# Schematic.net
KiCad netlist of a schematic drawn in EasyEDA
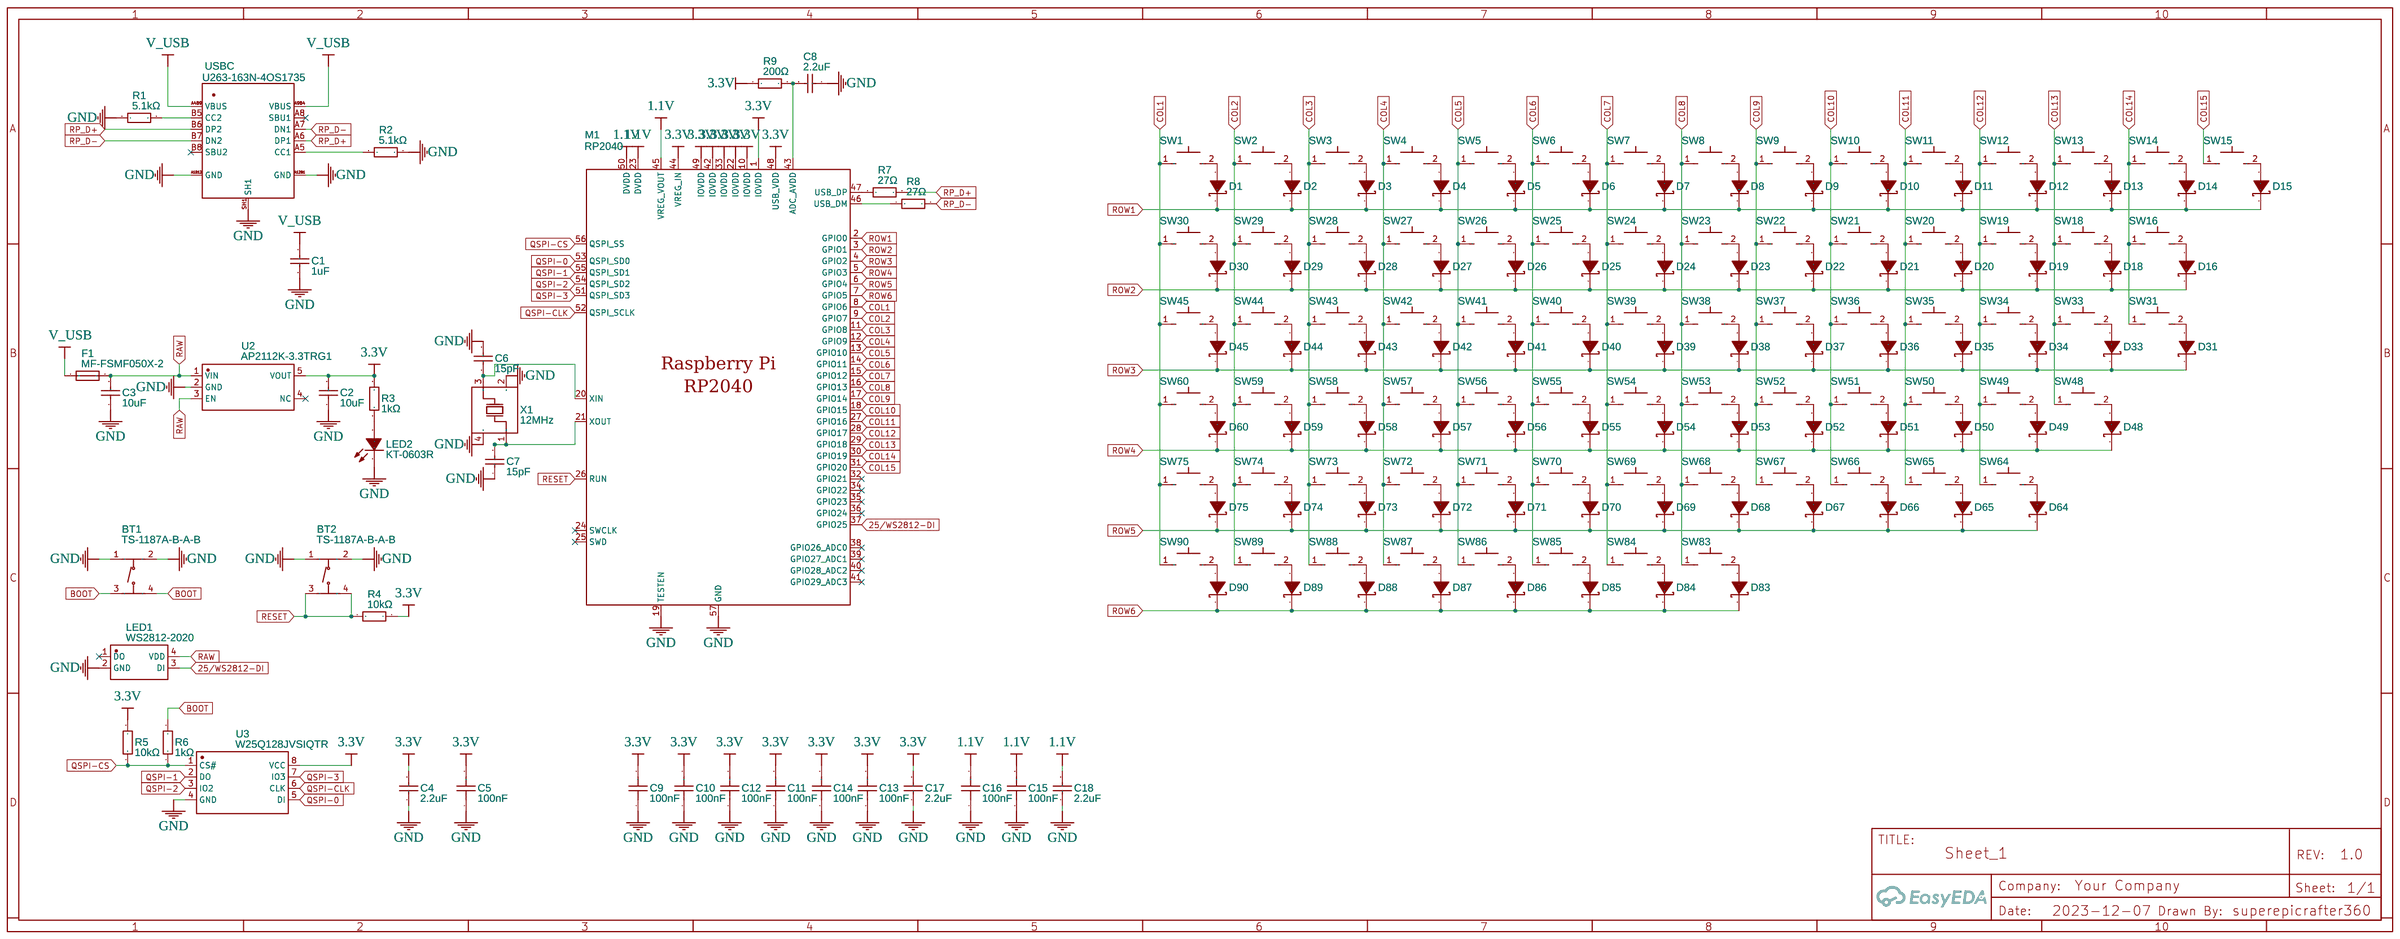
[diagram p0: schematic sheet]

(export (version "E")
  (design (tool "Eeschema 10.0.6"))
  (components
    (comp (ref "BT1")
      (value "TS-1187A-B-A-B")
      (fields (field (name "Manufacturer") "XKB Connectivity(中国星坤)"))
      (libsource (lib "") (part "TS-1187A-B-A-B"))
    )
    (comp (ref "BT2")
      (value "TS-1187A-B-A-B")
      (fields (field (name "Manufacturer") "XKB Connectivity(中国星坤)"))
      (libsource (lib "") (part "TS-1187A-B-A-B"))
    )
    (comp (ref "C1")
      (value "1uF")
      (fields
        (field (name "Manufacturer Part") "CL10A105KB8NNNC")
        (field (name "Manufacturer") "SAMSUNG(三星)")
      )
      (libsource (lib "") (part "CL10A105KB8NNNC"))
    )
    (comp (ref "C2")
      (value "10uF")
      (fields
        (field (name "Manufacturer Part") "CL31A106KBHNNNE")
        (field (name "Manufacturer") "SAMSUNG(三星)")
      )
      (libsource (lib "") (part "CL31A106KBHNNNE"))
    )
    (comp (ref "C3")
      (value "10uF")
      (fields
        (field (name "Manufacturer Part") "CL31A106KBHNNNE")
        (field (name "Manufacturer") "SAMSUNG(三星)")
      )
      (libsource (lib "") (part "CL31A106KBHNNNE"))
    )
    (comp (ref "C4")
      (value "2.2uF")
      (fields
        (field (name "Manufacturer Part") "CL10A225KO8NNNC")
        (field (name "Manufacturer") "SAMSUNG(三星)")
      )
      (libsource (lib "") (part "CL10A225KO8NNNC"))
    )
    (comp (ref "C5")
      (value "100nF")
      (fields
        (field (name "Manufacturer Part") "CC0603KRX7R9BB104")
        (field (name "Manufacturer") "YAGEO(国巨)")
      )
      (libsource (lib "") (part "CC0603KRX7R9BB104"))
    )
    (comp (ref "C6")
      (value "15pF")
      (fields (field (name "Manufacturer Part") "0402CG150J500NT") (field (name "Manufacturer") "FH(风华)"))
      (libsource (lib "") (part "0402CG150J500NT"))
    )
    (comp (ref "C7")
      (value "15pF")
      (fields (field (name "Manufacturer Part") "0402CG150J500NT") (field (name "Manufacturer") "FH(风华)"))
      (libsource (lib "") (part "0402CG150J500NT"))
    )
    (comp (ref "C8")
      (value "2.2uF")
      (fields
        (field (name "Manufacturer Part") "CL10A225KO8NNNC")
        (field (name "Manufacturer") "SAMSUNG(三星)")
      )
      (libsource (lib "") (part "CL10A225KO8NNNC_1"))
    )
    (comp (ref "C9")
      (value "100nF")
      (fields
        (field (name "Manufacturer Part") "CC0603KRX7R9BB104")
        (field (name "Manufacturer") "YAGEO(国巨)")
      )
      (libsource (lib "") (part "CC0603KRX7R9BB104"))
    )
    (comp (ref "C10")
      (value "100nF")
      (fields
        (field (name "Manufacturer Part") "CC0603KRX7R9BB104")
        (field (name "Manufacturer") "YAGEO(国巨)")
      )
      (libsource (lib "") (part "CC0603KRX7R9BB104"))
    )
    (comp (ref "C11")
      (value "100nF")
      (fields
        (field (name "Manufacturer Part") "CC0603KRX7R9BB104")
        (field (name "Manufacturer") "YAGEO(国巨)")
      )
      (libsource (lib "") (part "CC0603KRX7R9BB104"))
    )
    (comp (ref "C12")
      (value "100nF")
      (fields
        (field (name "Manufacturer Part") "CC0603KRX7R9BB104")
        (field (name "Manufacturer") "YAGEO(国巨)")
      )
      (libsource (lib "") (part "CC0603KRX7R9BB104"))
    )
    (comp (ref "C13")
      (value "100nF")
      (fields
        (field (name "Manufacturer Part") "CC0603KRX7R9BB104")
        (field (name "Manufacturer") "YAGEO(国巨)")
      )
      (libsource (lib "") (part "CC0603KRX7R9BB104"))
    )
    (comp (ref "C14")
      (value "100nF")
      (fields
        (field (name "Manufacturer Part") "CC0603KRX7R9BB104")
        (field (name "Manufacturer") "YAGEO(国巨)")
      )
      (libsource (lib "") (part "CC0603KRX7R9BB104"))
    )
    (comp (ref "C15")
      (value "100nF")
      (fields
        (field (name "Manufacturer Part") "CC0603KRX7R9BB104")
        (field (name "Manufacturer") "YAGEO(国巨)")
      )
      (libsource (lib "") (part "CC0603KRX7R9BB104"))
    )
    (comp (ref "C16")
      (value "100nF")
      (fields
        (field (name "Manufacturer Part") "CC0603KRX7R9BB104")
        (field (name "Manufacturer") "YAGEO(国巨)")
      )
      (libsource (lib "") (part "CC0603KRX7R9BB104"))
    )
    (comp (ref "C17")
      (value "2.2uF")
      (fields
        (field (name "Manufacturer Part") "CL10A225KO8NNNC")
        (field (name "Manufacturer") "SAMSUNG(三星)")
      )
      (libsource (lib "") (part "CL10A225KO8NNNC"))
    )
    (comp (ref "C18")
      (value "2.2uF")
      (fields
        (field (name "Manufacturer Part") "CL10A225KO8NNNC")
        (field (name "Manufacturer") "SAMSUNG(三星)")
      )
      (libsource (lib "") (part "CL10A225KO8NNNC"))
    )
    (comp (ref "D1")
      (value "SS210")
      (fields (field (name "Manufacturer") "MDD"))
      (libsource (lib "") (part "SS210"))
    )
    (comp (ref "D2")
      (value "SS210")
      (fields (field (name "Manufacturer") "MDD"))
      (libsource (lib "") (part "SS210"))
    )
    (comp (ref "D3")
      (value "SS210")
      (fields (field (name "Manufacturer") "MDD"))
      (libsource (lib "") (part "SS210"))
    )
    (comp (ref "D4")
      (value "SS210")
      (fields (field (name "Manufacturer") "MDD"))
      (libsource (lib "") (part "SS210"))
    )
    (comp (ref "D5")
      (value "SS210")
      (fields (field (name "Manufacturer") "MDD"))
      (libsource (lib "") (part "SS210"))
    )
    (comp (ref "D6")
      (value "SS210")
      (fields (field (name "Manufacturer") "MDD"))
      (libsource (lib "") (part "SS210"))
    )
    (comp (ref "D7")
      (value "SS210")
      (fields (field (name "Manufacturer") "MDD"))
      (libsource (lib "") (part "SS210"))
    )
    (comp (ref "D8")
      (value "SS210")
      (fields (field (name "Manufacturer") "MDD"))
      (libsource (lib "") (part "SS210"))
    )
    (comp (ref "D9")
      (value "SS210")
      (fields (field (name "Manufacturer") "MDD"))
      (libsource (lib "") (part "SS210"))
    )
    (comp (ref "D10")
      (value "SS210")
      (fields (field (name "Manufacturer") "MDD"))
      (libsource (lib "") (part "SS210"))
    )
    (comp (ref "D11")
      (value "SS210")
      (fields (field (name "Manufacturer") "MDD"))
      (libsource (lib "") (part "SS210"))
    )
    (comp (ref "D12")
      (value "SS210")
      (fields (field (name "Manufacturer") "MDD"))
      (libsource (lib "") (part "SS210"))
    )
    (comp (ref "D13")
      (value "SS210")
      (fields (field (name "Manufacturer") "MDD"))
      (libsource (lib "") (part "SS210"))
    )
    (comp (ref "D14")
      (value "SS210")
      (fields (field (name "Manufacturer") "MDD"))
      (libsource (lib "") (part "SS210"))
    )
    (comp (ref "D15")
      (value "SS210")
      (fields (field (name "Manufacturer") "MDD"))
      (libsource (lib "") (part "SS210"))
    )
    (comp (ref "D16")
      (value "SS210")
      (fields (field (name "Manufacturer") "MDD"))
      (libsource (lib "") (part "SS210"))
    )
    (comp (ref "D18")
      (value "SS210")
      (fields (field (name "Manufacturer") "MDD"))
      (libsource (lib "") (part "SS210"))
    )
    (comp (ref "D19")
      (value "SS210")
      (fields (field (name "Manufacturer") "MDD"))
      (libsource (lib "") (part "SS210"))
    )
    (comp (ref "D20")
      (value "SS210")
      (fields (field (name "Manufacturer") "MDD"))
      (libsource (lib "") (part "SS210"))
    )
    (comp (ref "D21")
      (value "SS210")
      (fields (field (name "Manufacturer") "MDD"))
      (libsource (lib "") (part "SS210"))
    )
    (comp (ref "D22")
      (value "SS210")
      (fields (field (name "Manufacturer") "MDD"))
      (libsource (lib "") (part "SS210"))
    )
    (comp (ref "D23")
      (value "SS210")
      (fields (field (name "Manufacturer") "MDD"))
      (libsource (lib "") (part "SS210"))
    )
    (comp (ref "D24")
      (value "SS210")
      (fields (field (name "Manufacturer") "MDD"))
      (libsource (lib "") (part "SS210"))
    )
    (comp (ref "D25")
      (value "SS210")
      (fields (field (name "Manufacturer") "MDD"))
      (libsource (lib "") (part "SS210"))
    )
    (comp (ref "D26")
      (value "SS210")
      (fields (field (name "Manufacturer") "MDD"))
      (libsource (lib "") (part "SS210"))
    )
    (comp (ref "D27")
      (value "SS210")
      (fields (field (name "Manufacturer") "MDD"))
      (libsource (lib "") (part "SS210"))
    )
    (comp (ref "D28")
      (value "SS210")
      (fields (field (name "Manufacturer") "MDD"))
      (libsource (lib "") (part "SS210"))
    )
    (comp (ref "D29")
      (value "SS210")
      (fields (field (name "Manufacturer") "MDD"))
      (libsource (lib "") (part "SS210"))
    )
    (comp (ref "D30")
      (value "SS210")
      (fields (field (name "Manufacturer") "MDD"))
      (libsource (lib "") (part "SS210"))
    )
    (comp (ref "D31")
      (value "SS210")
      (fields (field (name "Manufacturer") "MDD"))
      (libsource (lib "") (part "SS210"))
    )
    (comp (ref "D33")
      (value "SS210")
      (fields (field (name "Manufacturer") "MDD"))
      (libsource (lib "") (part "SS210"))
    )
    (comp (ref "D34")
      (value "SS210")
      (fields (field (name "Manufacturer") "MDD"))
      (libsource (lib "") (part "SS210"))
    )
    (comp (ref "D35")
      (value "SS210")
      (fields (field (name "Manufacturer") "MDD"))
      (libsource (lib "") (part "SS210"))
    )
    (comp (ref "D36")
      (value "SS210")
      (fields (field (name "Manufacturer") "MDD"))
      (libsource (lib "") (part "SS210"))
    )
    (comp (ref "D37")
      (value "SS210")
      (fields (field (name "Manufacturer") "MDD"))
      (libsource (lib "") (part "SS210"))
    )
    (comp (ref "D38")
      (value "SS210")
      (fields (field (name "Manufacturer") "MDD"))
      (libsource (lib "") (part "SS210"))
    )
    (comp (ref "D39")
      (value "SS210")
      (fields (field (name "Manufacturer") "MDD"))
      (libsource (lib "") (part "SS210"))
    )
    (comp (ref "D40")
      (value "SS210")
      (fields (field (name "Manufacturer") "MDD"))
      (libsource (lib "") (part "SS210"))
    )
    (comp (ref "D41")
      (value "SS210")
      (fields (field (name "Manufacturer") "MDD"))
      (libsource (lib "") (part "SS210"))
    )
    (comp (ref "D42")
      (value "SS210")
      (fields (field (name "Manufacturer") "MDD"))
      (libsource (lib "") (part "SS210"))
    )
    (comp (ref "D43")
      (value "SS210")
      (fields (field (name "Manufacturer") "MDD"))
      (libsource (lib "") (part "SS210"))
    )
    (comp (ref "D44")
      (value "SS210")
      (fields (field (name "Manufacturer") "MDD"))
      (libsource (lib "") (part "SS210"))
    )
    (comp (ref "D45")
      (value "SS210")
      (fields (field (name "Manufacturer") "MDD"))
      (libsource (lib "") (part "SS210"))
    )
    (comp (ref "D48")
      (value "SS210")
      (fields (field (name "Manufacturer") "MDD"))
      (libsource (lib "") (part "SS210"))
    )
    (comp (ref "D49")
      (value "SS210")
      (fields (field (name "Manufacturer") "MDD"))
      (libsource (lib "") (part "SS210"))
    )
    (comp (ref "D50")
      (value "SS210")
      (fields (field (name "Manufacturer") "MDD"))
      (libsource (lib "") (part "SS210"))
    )
    (comp (ref "D51")
      (value "SS210")
      (fields (field (name "Manufacturer") "MDD"))
      (libsource (lib "") (part "SS210"))
    )
    (comp (ref "D52")
      (value "SS210")
      (fields (field (name "Manufacturer") "MDD"))
      (libsource (lib "") (part "SS210"))
    )
    (comp (ref "D53")
      (value "SS210")
      (fields (field (name "Manufacturer") "MDD"))
      (libsource (lib "") (part "SS210"))
    )
    (comp (ref "D54")
      (value "SS210")
      (fields (field (name "Manufacturer") "MDD"))
      (libsource (lib "") (part "SS210"))
    )
    (comp (ref "D55")
      (value "SS210")
      (fields (field (name "Manufacturer") "MDD"))
      (libsource (lib "") (part "SS210"))
    )
    (comp (ref "D56")
      (value "SS210")
      (fields (field (name "Manufacturer") "MDD"))
      (libsource (lib "") (part "SS210"))
    )
    (comp (ref "D57")
      (value "SS210")
      (fields (field (name "Manufacturer") "MDD"))
      (libsource (lib "") (part "SS210"))
    )
    (comp (ref "D58")
      (value "SS210")
      (fields (field (name "Manufacturer") "MDD"))
      (libsource (lib "") (part "SS210"))
    )
    (comp (ref "D59")
      (value "SS210")
      (fields (field (name "Manufacturer") "MDD"))
      (libsource (lib "") (part "SS210"))
    )
    (comp (ref "D60")
      (value "SS210")
      (fields (field (name "Manufacturer") "MDD"))
      (libsource (lib "") (part "SS210"))
    )
    (comp (ref "D64")
      (value "SS210")
      (fields (field (name "Manufacturer") "MDD"))
      (libsource (lib "") (part "SS210"))
    )
    (comp (ref "D65")
      (value "SS210")
      (fields (field (name "Manufacturer") "MDD"))
      (libsource (lib "") (part "SS210"))
    )
    (comp (ref "D66")
      (value "SS210")
      (fields (field (name "Manufacturer") "MDD"))
      (libsource (lib "") (part "SS210"))
    )
    (comp (ref "D67")
      (value "SS210")
      (fields (field (name "Manufacturer") "MDD"))
      (libsource (lib "") (part "SS210"))
    )
    (comp (ref "D68")
      (value "SS210")
      (fields (field (name "Manufacturer") "MDD"))
      (libsource (lib "") (part "SS210"))
    )
    (comp (ref "D69")
      (value "SS210")
      (fields (field (name "Manufacturer") "MDD"))
      (libsource (lib "") (part "SS210"))
    )
    (comp (ref "D70")
      (value "SS210")
      (fields (field (name "Manufacturer") "MDD"))
      (libsource (lib "") (part "SS210"))
    )
    (comp (ref "D71")
      (value "SS210")
      (fields (field (name "Manufacturer") "MDD"))
      (libsource (lib "") (part "SS210"))
    )
    (comp (ref "D72")
      (value "SS210")
      (fields (field (name "Manufacturer") "MDD"))
      (libsource (lib "") (part "SS210"))
    )
    (comp (ref "D73")
      (value "SS210")
      (fields (field (name "Manufacturer") "MDD"))
      (libsource (lib "") (part "SS210"))
    )
    (comp (ref "D74")
      (value "SS210")
      (fields (field (name "Manufacturer") "MDD"))
      (libsource (lib "") (part "SS210"))
    )
    (comp (ref "D75")
      (value "SS210")
      (fields (field (name "Manufacturer") "MDD"))
      (libsource (lib "") (part "SS210"))
    )
    (comp (ref "D83")
      (value "SS210")
      (fields (field (name "Manufacturer") "MDD"))
      (libsource (lib "") (part "SS210"))
    )
    (comp (ref "D84")
      (value "SS210")
      (fields (field (name "Manufacturer") "MDD"))
      (libsource (lib "") (part "SS210"))
    )
    (comp (ref "D85")
      (value "SS210")
      (fields (field (name "Manufacturer") "MDD"))
      (libsource (lib "") (part "SS210"))
    )
    (comp (ref "D86")
      (value "SS210")
      (fields (field (name "Manufacturer") "MDD"))
      (libsource (lib "") (part "SS210"))
    )
    (comp (ref "D87")
      (value "SS210")
      (fields (field (name "Manufacturer") "MDD"))
      (libsource (lib "") (part "SS210"))
    )
    (comp (ref "D88")
      (value "SS210")
      (fields (field (name "Manufacturer") "MDD"))
      (libsource (lib "") (part "SS210"))
    )
    (comp (ref "D89")
      (value "SS210")
      (fields (field (name "Manufacturer") "MDD"))
      (libsource (lib "") (part "SS210"))
    )
    (comp (ref "D90")
      (value "SS210")
      (fields (field (name "Manufacturer") "MDD"))
      (libsource (lib "") (part "SS210"))
    )
    (comp (ref "F1")
      (value "MF-FSMF050X-2")
      (fields (field (name "Manufacturer") "BOURNS"))
      (libsource (lib "") (part "MF-FSMF050X-2"))
    )
    (comp (ref "LED1") (value "WS2812-2020") (libsource (lib "") (part "WS2812-2020")))
    (comp (ref "LED2")
      (value "KT-0603R")
      (fields (field (name "Manufacturer") "KENTO"))
      (libsource (lib "") (part "KT-0603R"))
    )
    (comp (ref "M1")
      (value "RP2040")
      (fields (field (name "Manufacturer") "Raspberry Pi(树莓派)"))
      (libsource (lib "") (part "RP2040"))
    )
    (comp (ref "R1")
      (value "5.1kΩ")
      (fields
        (field (name "Manufacturer Part") "0603WAF5101T5E")
        (field (name "Manufacturer") "UNI-ROYAL(厚声)")
      )
      (libsource (lib "") (part "0603WAF5101T5E_1"))
    )
    (comp (ref "R2")
      (value "5.1kΩ")
      (fields
        (field (name "Manufacturer Part") "0603WAF5101T5E")
        (field (name "Manufacturer") "UNI-ROYAL(厚声)")
      )
      (libsource (lib "") (part "0603WAF5101T5E"))
    )
    (comp (ref "R3")
      (value "1kΩ")
      (fields
        (field (name "Manufacturer Part") "0603WAF1001T5E")
        (field (name "Manufacturer") "UNI-ROYAL(厚声)")
      )
      (libsource (lib "") (part "0603WAF1001T5E"))
    )
    (comp (ref "R4")
      (value "10kΩ")
      (fields
        (field (name "Manufacturer Part") "0603WAF1002T5E")
        (field (name "Manufacturer") "UNI-ROYAL(厚声)")
      )
      (libsource (lib "") (part "0603WAF1002T5E"))
    )
    (comp (ref "R5")
      (value "10kΩ")
      (fields
        (field (name "Manufacturer Part") "0603WAF1002T5E")
        (field (name "Manufacturer") "UNI-ROYAL(厚声)")
      )
      (libsource (lib "") (part "0603WAF1002T5E_1"))
    )
    (comp (ref "R6")
      (value "1kΩ")
      (fields
        (field (name "Manufacturer Part") "0603WAF1001T5E")
        (field (name "Manufacturer") "UNI-ROYAL(厚声)")
      )
      (libsource (lib "") (part "0603WAF1001T5E"))
    )
    (comp (ref "R7")
      (value "27Ω")
      (fields
        (field (name "Manufacturer Part") "0603WAF270JT5E")
        (field (name "Manufacturer") "UNI-ROYAL(厚声)")
      )
      (libsource (lib "") (part "0603WAF270JT5E"))
    )
    (comp (ref "R8")
      (value "27Ω")
      (fields
        (field (name "Manufacturer Part") "0603WAF270JT5E")
        (field (name "Manufacturer") "UNI-ROYAL(厚声)")
      )
      (libsource (lib "") (part "0603WAF270JT5E"))
    )
    (comp (ref "R9")
      (value "200Ω")
      (fields
        (field (name "Manufacturer Part") "0603WAF2000T5E")
        (field (name "Manufacturer") "UNI-ROYAL(厚声)")
      )
      (libsource (lib "") (part "0603WAF2000T5E"))
    )
    (comp (ref "SW1")
      (value "CPG151101S11-16")
      (fields (field (name "Manufacturer") "Kailh(凯华)"))
      (libsource (lib "") (part "CPG151101S11-16"))
    )
    (comp (ref "SW2")
      (value "CPG151101S11-16")
      (fields (field (name "Manufacturer") "Kailh(凯华)"))
      (libsource (lib "") (part "CPG151101S11-16"))
    )
    (comp (ref "SW3")
      (value "CPG151101S11-16")
      (fields (field (name "Manufacturer") "Kailh(凯华)"))
      (libsource (lib "") (part "CPG151101S11-16"))
    )
    (comp (ref "SW4")
      (value "CPG151101S11-16")
      (fields (field (name "Manufacturer") "Kailh(凯华)"))
      (libsource (lib "") (part "CPG151101S11-16"))
    )
    (comp (ref "SW5")
      (value "CPG151101S11-16")
      (fields (field (name "Manufacturer") "Kailh(凯华)"))
      (libsource (lib "") (part "CPG151101S11-16"))
    )
    (comp (ref "SW6")
      (value "CPG151101S11-16")
      (fields (field (name "Manufacturer") "Kailh(凯华)"))
      (libsource (lib "") (part "CPG151101S11-16"))
    )
    (comp (ref "SW7")
      (value "CPG151101S11-16")
      (fields (field (name "Manufacturer") "Kailh(凯华)"))
      (libsource (lib "") (part "CPG151101S11-16"))
    )
    (comp (ref "SW8")
      (value "CPG151101S11-16")
      (fields (field (name "Manufacturer") "Kailh(凯华)"))
      (libsource (lib "") (part "CPG151101S11-16"))
    )
    (comp (ref "SW9")
      (value "CPG151101S11-16")
      (fields (field (name "Manufacturer") "Kailh(凯华)"))
      (libsource (lib "") (part "CPG151101S11-16"))
    )
    (comp (ref "SW10")
      (value "CPG151101S11-16")
      (fields (field (name "Manufacturer") "Kailh(凯华)"))
      (libsource (lib "") (part "CPG151101S11-16"))
    )
    (comp (ref "SW11")
      (value "CPG151101S11-16")
      (fields (field (name "Manufacturer") "Kailh(凯华)"))
      (libsource (lib "") (part "CPG151101S11-16"))
    )
    (comp (ref "SW12")
      (value "CPG151101S11-16")
      (fields (field (name "Manufacturer") "Kailh(凯华)"))
      (libsource (lib "") (part "CPG151101S11-16"))
    )
    (comp (ref "SW13")
      (value "CPG151101S11-16")
      (fields (field (name "Manufacturer") "Kailh(凯华)"))
      (libsource (lib "") (part "CPG151101S11-16"))
    )
    (comp (ref "SW14")
      (value "CPG151101S11-16")
      (fields (field (name "Manufacturer") "Kailh(凯华)"))
      (libsource (lib "") (part "CPG151101S11-16"))
    )
    (comp (ref "SW15")
      (value "CPG151101S11-16")
      (fields (field (name "Manufacturer") "Kailh(凯华)"))
      (libsource (lib "") (part "CPG151101S11-16"))
    )
    (comp (ref "SW16")
      (value "CPG151101S11-16")
      (fields (field (name "Manufacturer") "Kailh(凯华)"))
      (libsource (lib "") (part "CPG151101S11-16"))
    )
    (comp (ref "SW18")
      (value "CPG151101S11-16")
      (fields (field (name "Manufacturer") "Kailh(凯华)"))
      (libsource (lib "") (part "CPG151101S11-16"))
    )
    (comp (ref "SW19")
      (value "CPG151101S11-16")
      (fields (field (name "Manufacturer") "Kailh(凯华)"))
      (libsource (lib "") (part "CPG151101S11-16"))
    )
    (comp (ref "SW20")
      (value "CPG151101S11-16")
      (fields (field (name "Manufacturer") "Kailh(凯华)"))
      (libsource (lib "") (part "CPG151101S11-16"))
    )
    (comp (ref "SW21")
      (value "CPG151101S11-16")
      (fields (field (name "Manufacturer") "Kailh(凯华)"))
      (libsource (lib "") (part "CPG151101S11-16"))
    )
    (comp (ref "SW22")
      (value "CPG151101S11-16")
      (fields (field (name "Manufacturer") "Kailh(凯华)"))
      (libsource (lib "") (part "CPG151101S11-16"))
    )
    (comp (ref "SW23")
      (value "CPG151101S11-16")
      (fields (field (name "Manufacturer") "Kailh(凯华)"))
      (libsource (lib "") (part "CPG151101S11-16"))
    )
    (comp (ref "SW24")
      (value "CPG151101S11-16")
      (fields (field (name "Manufacturer") "Kailh(凯华)"))
      (libsource (lib "") (part "CPG151101S11-16"))
    )
    (comp (ref "SW25")
      (value "CPG151101S11-16")
      (fields (field (name "Manufacturer") "Kailh(凯华)"))
      (libsource (lib "") (part "CPG151101S11-16"))
    )
    (comp (ref "SW26")
      (value "CPG151101S11-16")
      (fields (field (name "Manufacturer") "Kailh(凯华)"))
      (libsource (lib "") (part "CPG151101S11-16"))
    )
    (comp (ref "SW27")
      (value "CPG151101S11-16")
      (fields (field (name "Manufacturer") "Kailh(凯华)"))
      (libsource (lib "") (part "CPG151101S11-16"))
    )
    (comp (ref "SW28")
      (value "CPG151101S11-16")
      (fields (field (name "Manufacturer") "Kailh(凯华)"))
      (libsource (lib "") (part "CPG151101S11-16"))
    )
    (comp (ref "SW29")
      (value "CPG151101S11-16")
      (fields (field (name "Manufacturer") "Kailh(凯华)"))
      (libsource (lib "") (part "CPG151101S11-16"))
    )
    (comp (ref "SW30")
      (value "CPG151101S11-16")
      (fields (field (name "Manufacturer") "Kailh(凯华)"))
      (libsource (lib "") (part "CPG151101S11-16"))
    )
    (comp (ref "SW31")
      (value "CPG151101S11-16")
      (fields (field (name "Manufacturer") "Kailh(凯华)"))
      (libsource (lib "") (part "CPG151101S11-16"))
    )
    (comp (ref "SW33")
      (value "CPG151101S11-16")
      (fields (field (name "Manufacturer") "Kailh(凯华)"))
      (libsource (lib "") (part "CPG151101S11-16"))
    )
    (comp (ref "SW34")
      (value "CPG151101S11-16")
      (fields (field (name "Manufacturer") "Kailh(凯华)"))
      (libsource (lib "") (part "CPG151101S11-16"))
    )
    (comp (ref "SW35")
      (value "CPG151101S11-16")
      (fields (field (name "Manufacturer") "Kailh(凯华)"))
      (libsource (lib "") (part "CPG151101S11-16"))
    )
    (comp (ref "SW36")
      (value "CPG151101S11-16")
      (fields (field (name "Manufacturer") "Kailh(凯华)"))
      (libsource (lib "") (part "CPG151101S11-16"))
    )
    (comp (ref "SW37")
      (value "CPG151101S11-16")
      (fields (field (name "Manufacturer") "Kailh(凯华)"))
      (libsource (lib "") (part "CPG151101S11-16"))
    )
    (comp (ref "SW38")
      (value "CPG151101S11-16")
      (fields (field (name "Manufacturer") "Kailh(凯华)"))
      (libsource (lib "") (part "CPG151101S11-16"))
    )
    (comp (ref "SW39")
      (value "CPG151101S11-16")
      (fields (field (name "Manufacturer") "Kailh(凯华)"))
      (libsource (lib "") (part "CPG151101S11-16"))
    )
    (comp (ref "SW40")
      (value "CPG151101S11-16")
      (fields (field (name "Manufacturer") "Kailh(凯华)"))
      (libsource (lib "") (part "CPG151101S11-16"))
    )
    (comp (ref "SW41")
      (value "CPG151101S11-16")
      (fields (field (name "Manufacturer") "Kailh(凯华)"))
      (libsource (lib "") (part "CPG151101S11-16"))
    )
    (comp (ref "SW42")
      (value "CPG151101S11-16")
      (fields (field (name "Manufacturer") "Kailh(凯华)"))
      (libsource (lib "") (part "CPG151101S11-16"))
    )
    (comp (ref "SW43")
      (value "CPG151101S11-16")
      (fields (field (name "Manufacturer") "Kailh(凯华)"))
      (libsource (lib "") (part "CPG151101S11-16"))
    )
    (comp (ref "SW44")
      (value "CPG151101S11-16")
      (fields (field (name "Manufacturer") "Kailh(凯华)"))
      (libsource (lib "") (part "CPG151101S11-16"))
    )
    (comp (ref "SW45")
      (value "CPG151101S11-16")
      (fields (field (name "Manufacturer") "Kailh(凯华)"))
      (libsource (lib "") (part "CPG151101S11-16"))
    )
    (comp (ref "SW48")
      (value "CPG151101S11-16")
      (fields (field (name "Manufacturer") "Kailh(凯华)"))
      (libsource (lib "") (part "CPG151101S11-16"))
    )
    (comp (ref "SW49")
      (value "CPG151101S11-16")
      (fields (field (name "Manufacturer") "Kailh(凯华)"))
      (libsource (lib "") (part "CPG151101S11-16"))
    )
    (comp (ref "SW50")
      (value "CPG151101S11-16")
      (fields (field (name "Manufacturer") "Kailh(凯华)"))
      (libsource (lib "") (part "CPG151101S11-16"))
    )
    (comp (ref "SW51")
      (value "CPG151101S11-16")
      (fields (field (name "Manufacturer") "Kailh(凯华)"))
      (libsource (lib "") (part "CPG151101S11-16"))
    )
    (comp (ref "SW52")
      (value "CPG151101S11-16")
      (fields (field (name "Manufacturer") "Kailh(凯华)"))
      (libsource (lib "") (part "CPG151101S11-16"))
    )
    (comp (ref "SW53")
      (value "CPG151101S11-16")
      (fields (field (name "Manufacturer") "Kailh(凯华)"))
      (libsource (lib "") (part "CPG151101S11-16"))
    )
    (comp (ref "SW54")
      (value "CPG151101S11-16")
      (fields (field (name "Manufacturer") "Kailh(凯华)"))
      (libsource (lib "") (part "CPG151101S11-16"))
    )
    (comp (ref "SW55")
      (value "CPG151101S11-16")
      (fields (field (name "Manufacturer") "Kailh(凯华)"))
      (libsource (lib "") (part "CPG151101S11-16"))
    )
    (comp (ref "SW56")
      (value "CPG151101S11-16")
      (fields (field (name "Manufacturer") "Kailh(凯华)"))
      (libsource (lib "") (part "CPG151101S11-16"))
    )
    (comp (ref "SW57")
      (value "CPG151101S11-16")
      (fields (field (name "Manufacturer") "Kailh(凯华)"))
      (libsource (lib "") (part "CPG151101S11-16"))
    )
    (comp (ref "SW58")
      (value "CPG151101S11-16")
      (fields (field (name "Manufacturer") "Kailh(凯华)"))
      (libsource (lib "") (part "CPG151101S11-16"))
    )
    (comp (ref "SW59")
      (value "CPG151101S11-16")
      (fields (field (name "Manufacturer") "Kailh(凯华)"))
      (libsource (lib "") (part "CPG151101S11-16"))
    )
    (comp (ref "SW60")
      (value "CPG151101S11-16")
      (fields (field (name "Manufacturer") "Kailh(凯华)"))
      (libsource (lib "") (part "CPG151101S11-16"))
    )
    (comp (ref "SW64")
      (value "CPG151101S11-16")
      (fields (field (name "Manufacturer") "Kailh(凯华)"))
      (libsource (lib "") (part "CPG151101S11-16"))
    )
    (comp (ref "SW65")
      (value "CPG151101S11-16")
      (fields (field (name "Manufacturer") "Kailh(凯华)"))
      (libsource (lib "") (part "CPG151101S11-16"))
    )
    (comp (ref "SW66")
      (value "CPG151101S11-16")
      (fields (field (name "Manufacturer") "Kailh(凯华)"))
      (libsource (lib "") (part "CPG151101S11-16"))
    )
    (comp (ref "SW67")
      (value "CPG151101S11-16")
      (fields (field (name "Manufacturer") "Kailh(凯华)"))
      (libsource (lib "") (part "CPG151101S11-16"))
    )
    (comp (ref "SW68")
      (value "CPG151101S11-16")
      (fields (field (name "Manufacturer") "Kailh(凯华)"))
      (libsource (lib "") (part "CPG151101S11-16"))
    )
    (comp (ref "SW69")
      (value "CPG151101S11-16")
      (fields (field (name "Manufacturer") "Kailh(凯华)"))
      (libsource (lib "") (part "CPG151101S11-16"))
    )
    (comp (ref "SW70")
      (value "CPG151101S11-16")
      (fields (field (name "Manufacturer") "Kailh(凯华)"))
      (libsource (lib "") (part "CPG151101S11-16"))
    )
    (comp (ref "SW71")
      (value "CPG151101S11-16")
      (fields (field (name "Manufacturer") "Kailh(凯华)"))
      (libsource (lib "") (part "CPG151101S11-16"))
    )
    (comp (ref "SW72")
      (value "CPG151101S11-16")
      (fields (field (name "Manufacturer") "Kailh(凯华)"))
      (libsource (lib "") (part "CPG151101S11-16"))
    )
    (comp (ref "SW73")
      (value "CPG151101S11-16")
      (fields (field (name "Manufacturer") "Kailh(凯华)"))
      (libsource (lib "") (part "CPG151101S11-16"))
    )
    (comp (ref "SW74")
      (value "CPG151101S11-16")
      (fields (field (name "Manufacturer") "Kailh(凯华)"))
      (libsource (lib "") (part "CPG151101S11-16"))
    )
    (comp (ref "SW75")
      (value "CPG151101S11-16")
      (fields (field (name "Manufacturer") "Kailh(凯华)"))
      (libsource (lib "") (part "CPG151101S11-16"))
    )
    (comp (ref "SW83")
      (value "CPG151101S11-16")
      (fields (field (name "Manufacturer") "Kailh(凯华)"))
      (libsource (lib "") (part "CPG151101S11-16"))
    )
    (comp (ref "SW84")
      (value "CPG151101S11-16")
      (fields (field (name "Manufacturer") "Kailh(凯华)"))
      (libsource (lib "") (part "CPG151101S11-16"))
    )
    (comp (ref "SW85")
      (value "CPG151101S11-16")
      (fields (field (name "Manufacturer") "Kailh(凯华)"))
      (libsource (lib "") (part "CPG151101S11-16"))
    )
    (comp (ref "SW86")
      (value "CPG151101S11-16")
      (fields (field (name "Manufacturer") "Kailh(凯华)"))
      (libsource (lib "") (part "CPG151101S11-16"))
    )
    (comp (ref "SW87")
      (value "CPG151101S11-16")
      (fields (field (name "Manufacturer") "Kailh(凯华)"))
      (libsource (lib "") (part "CPG151101S11-16"))
    )
    (comp (ref "SW88")
      (value "CPG151101S11-16")
      (fields (field (name "Manufacturer") "Kailh(凯华)"))
      (libsource (lib "") (part "CPG151101S11-16"))
    )
    (comp (ref "SW89")
      (value "CPG151101S11-16")
      (fields (field (name "Manufacturer") "Kailh(凯华)"))
      (libsource (lib "") (part "CPG151101S11-16"))
    )
    (comp (ref "SW90")
      (value "CPG151101S11-16")
      (fields (field (name "Manufacturer") "Kailh(凯华)"))
      (libsource (lib "") (part "CPG151101S11-16"))
    )
    (comp (ref "U2")
      (value "AP2112K-3.3TRG1")
      (fields (field (name "Manufacturer") "DIODES(美台)"))
      (libsource (lib "") (part "AP2112K-3.3TRG1"))
    )
    (comp (ref "U3")
      (value "W25Q128JVSIQTR")
      (fields (field (name "Manufacturer Part") "W25Q128JVSIQ") (field (name "Manufacturer") "WINBOND(华邦)"))
      (libsource (lib "") (part "W25Q128JVSIQTR"))
    )
    (comp (ref "USBC")
      (value "U263-163N-4OS1735")
      (fields (field (name "Manufacturer") "XKB Connectivity(中国星坤)"))
      (libsource (lib "") (part "U263-163N-4OS1735"))
    )
    (comp (ref "X1")
      (value "12MHz")
      (fields (field (name "Manufacturer Part") "X322512MSB4SI") (field (name "Manufacturer") "YXC(扬兴晶振)"))
      (libsource (lib "") (part "X322512MSB4SI"))
    )
  )
  (nets
    (net (code "1") (name "1.1V") (class "Default")
      (node (ref "C15") (pin "2") (pinfunction "2_2") (pintype "unspecified"))
      (node (ref "C16") (pin "2") (pinfunction "2_2") (pintype "unspecified"))
      (node (ref "C18") (pin "2") (pinfunction "2_2") (pintype "input"))
      (node (ref "M1") (pin "23") (pinfunction "DVDD_23") (pintype "bidirectional"))
      (node (ref "M1") (pin "45") (pinfunction "VREG_VOUT_45") (pintype "bidirectional"))
      (node (ref "M1") (pin "50") (pinfunction "DVDD_50") (pintype "bidirectional"))
    )
    (net (code "2") (name "3.3V") (class "Default")
      (node (ref "C10") (pin "2") (pinfunction "2_2") (pintype "unspecified"))
      (node (ref "C11") (pin "2") (pinfunction "2_2") (pintype "unspecified"))
      (node (ref "C12") (pin "2") (pinfunction "2_2") (pintype "unspecified"))
      (node (ref "C13") (pin "2") (pinfunction "2_2") (pintype "unspecified"))
      (node (ref "C14") (pin "2") (pinfunction "2_2") (pintype "unspecified"))
      (node (ref "C17") (pin "2") (pinfunction "2_2") (pintype "input"))
      (node (ref "C2") (pin "2") (pinfunction "2_2") (pintype "input"))
      (node (ref "C4") (pin "2") (pinfunction "2_2") (pintype "input"))
      (node (ref "C5") (pin "2") (pinfunction "2_2") (pintype "unspecified"))
      (node (ref "C9") (pin "2") (pinfunction "2_2") (pintype "unspecified"))
      (node (ref "M1") (pin "1") (pinfunction "IOVDD_1") (pintype "bidirectional"))
      (node (ref "M1") (pin "10") (pinfunction "IOVDD_10") (pintype "bidirectional"))
      (node (ref "M1") (pin "22") (pinfunction "IOVDD_22") (pintype "bidirectional"))
      (node (ref "M1") (pin "33") (pinfunction "IOVDD_33") (pintype "bidirectional"))
      (node (ref "M1") (pin "42") (pinfunction "IOVDD_42") (pintype "bidirectional"))
      (node (ref "M1") (pin "44") (pinfunction "VREG_IN_44") (pintype "bidirectional"))
      (node (ref "M1") (pin "48") (pinfunction "USB_VDD_48") (pintype "bidirectional"))
      (node (ref "M1") (pin "49") (pinfunction "IOVDD_49") (pintype "bidirectional"))
      (node (ref "R3") (pin "2") (pinfunction "2_2") (pintype "input"))
      (node (ref "R4") (pin "2") (pinfunction "2_2") (pintype "input"))
      (node (ref "R5") (pin "2") (pinfunction "2_2") (pintype "input"))
      (node (ref "R9") (pin "1") (pinfunction "1_1") (pintype "input"))
      (node (ref "U2") (pin "5") (pinfunction "VOUT_5") (pintype "unspecified"))
      (node (ref "U3") (pin "8") (pinfunction "VCC_8") (pintype "unspecified"))
    )
    (net (code "3") (name "25{slash}WS2812-DI") (class "Default")
      (node (ref "LED1") (pin "3") (pinfunction "DI_3") (pintype "unspecified"))
      (node (ref "M1") (pin "37") (pinfunction "GPIO25_37") (pintype "bidirectional"))
    )
    (net (code "4") (name "BOOT") (class "Default")
      (node (ref "BT1") (pin "3") (pinfunction "C_3") (pintype "unspecified"))
      (node (ref "BT1") (pin "4") (pinfunction "D_4") (pintype "unspecified"))
      (node (ref "R6") (pin "2") (pinfunction "2_2") (pintype "input"))
    )
    (net (code "5") (name "COL1") (class "Default")
      (node (ref "M1") (pin "8") (pinfunction "GPIO6_8") (pintype "bidirectional"))
      (node (ref "SW1") (pin "1") (pinfunction "1_1") (pintype "input"))
      (node (ref "SW30") (pin "1") (pinfunction "1_1") (pintype "input"))
      (node (ref "SW45") (pin "1") (pinfunction "1_1") (pintype "input"))
      (node (ref "SW60") (pin "1") (pinfunction "1_1") (pintype "input"))
      (node (ref "SW75") (pin "1") (pinfunction "1_1") (pintype "input"))
      (node (ref "SW90") (pin "1") (pinfunction "1_1") (pintype "input"))
    )
    (net (code "6") (name "COL2") (class "Default")
      (node (ref "M1") (pin "9") (pinfunction "GPIO7_9") (pintype "bidirectional"))
      (node (ref "SW2") (pin "1") (pinfunction "1_1") (pintype "input"))
      (node (ref "SW29") (pin "1") (pinfunction "1_1") (pintype "input"))
      (node (ref "SW44") (pin "1") (pinfunction "1_1") (pintype "input"))
      (node (ref "SW59") (pin "1") (pinfunction "1_1") (pintype "input"))
      (node (ref "SW74") (pin "1") (pinfunction "1_1") (pintype "input"))
      (node (ref "SW89") (pin "1") (pinfunction "1_1") (pintype "input"))
    )
    (net (code "7") (name "COL3") (class "Default")
      (node (ref "M1") (pin "11") (pinfunction "GPIO8_11") (pintype "bidirectional"))
      (node (ref "SW28") (pin "1") (pinfunction "1_1") (pintype "input"))
      (node (ref "SW3") (pin "1") (pinfunction "1_1") (pintype "input"))
      (node (ref "SW43") (pin "1") (pinfunction "1_1") (pintype "input"))
      (node (ref "SW58") (pin "1") (pinfunction "1_1") (pintype "input"))
      (node (ref "SW73") (pin "1") (pinfunction "1_1") (pintype "input"))
      (node (ref "SW88") (pin "1") (pinfunction "1_1") (pintype "input"))
    )
    (net (code "8") (name "COL4") (class "Default")
      (node (ref "M1") (pin "12") (pinfunction "GPIO9_12") (pintype "bidirectional"))
      (node (ref "SW27") (pin "1") (pinfunction "1_1") (pintype "input"))
      (node (ref "SW4") (pin "1") (pinfunction "1_1") (pintype "input"))
      (node (ref "SW42") (pin "1") (pinfunction "1_1") (pintype "input"))
      (node (ref "SW57") (pin "1") (pinfunction "1_1") (pintype "input"))
      (node (ref "SW72") (pin "1") (pinfunction "1_1") (pintype "input"))
      (node (ref "SW87") (pin "1") (pinfunction "1_1") (pintype "input"))
    )
    (net (code "9") (name "COL5") (class "Default")
      (node (ref "M1") (pin "13") (pinfunction "GPIO10_13") (pintype "bidirectional"))
      (node (ref "SW26") (pin "1") (pinfunction "1_1") (pintype "input"))
      (node (ref "SW41") (pin "1") (pinfunction "1_1") (pintype "input"))
      (node (ref "SW5") (pin "1") (pinfunction "1_1") (pintype "input"))
      (node (ref "SW56") (pin "1") (pinfunction "1_1") (pintype "input"))
      (node (ref "SW71") (pin "1") (pinfunction "1_1") (pintype "input"))
      (node (ref "SW86") (pin "1") (pinfunction "1_1") (pintype "input"))
    )
    (net (code "10") (name "COL6") (class "Default")
      (node (ref "M1") (pin "14") (pinfunction "GPIO11_14") (pintype "bidirectional"))
      (node (ref "SW25") (pin "1") (pinfunction "1_1") (pintype "input"))
      (node (ref "SW40") (pin "1") (pinfunction "1_1") (pintype "input"))
      (node (ref "SW55") (pin "1") (pinfunction "1_1") (pintype "input"))
      (node (ref "SW6") (pin "1") (pinfunction "1_1") (pintype "input"))
      (node (ref "SW70") (pin "1") (pinfunction "1_1") (pintype "input"))
      (node (ref "SW85") (pin "1") (pinfunction "1_1") (pintype "input"))
    )
    (net (code "11") (name "COL7") (class "Default")
      (node (ref "M1") (pin "15") (pinfunction "GPIO12_15") (pintype "bidirectional"))
      (node (ref "SW24") (pin "1") (pinfunction "1_1") (pintype "input"))
      (node (ref "SW39") (pin "1") (pinfunction "1_1") (pintype "input"))
      (node (ref "SW54") (pin "1") (pinfunction "1_1") (pintype "input"))
      (node (ref "SW69") (pin "1") (pinfunction "1_1") (pintype "input"))
      (node (ref "SW7") (pin "1") (pinfunction "1_1") (pintype "input"))
      (node (ref "SW84") (pin "1") (pinfunction "1_1") (pintype "input"))
    )
    (net (code "12") (name "COL8") (class "Default")
      (node (ref "M1") (pin "16") (pinfunction "GPIO13_16") (pintype "bidirectional"))
      (node (ref "SW23") (pin "1") (pinfunction "1_1") (pintype "input"))
      (node (ref "SW38") (pin "1") (pinfunction "1_1") (pintype "input"))
      (node (ref "SW53") (pin "1") (pinfunction "1_1") (pintype "input"))
      (node (ref "SW68") (pin "1") (pinfunction "1_1") (pintype "input"))
      (node (ref "SW8") (pin "1") (pinfunction "1_1") (pintype "input"))
      (node (ref "SW83") (pin "1") (pinfunction "1_1") (pintype "input"))
    )
    (net (code "13") (name "COL9") (class "Default")
      (node (ref "M1") (pin "17") (pinfunction "GPIO14_17") (pintype "bidirectional"))
      (node (ref "SW22") (pin "1") (pinfunction "1_1") (pintype "input"))
      (node (ref "SW37") (pin "1") (pinfunction "1_1") (pintype "input"))
      (node (ref "SW52") (pin "1") (pinfunction "1_1") (pintype "input"))
      (node (ref "SW67") (pin "1") (pinfunction "1_1") (pintype "input"))
      (node (ref "SW9") (pin "1") (pinfunction "1_1") (pintype "input"))
    )
    (net (code "14") (name "COL10") (class "Default")
      (node (ref "M1") (pin "18") (pinfunction "GPIO15_18") (pintype "bidirectional"))
      (node (ref "SW10") (pin "1") (pinfunction "1_1") (pintype "input"))
      (node (ref "SW21") (pin "1") (pinfunction "1_1") (pintype "input"))
      (node (ref "SW36") (pin "1") (pinfunction "1_1") (pintype "input"))
      (node (ref "SW51") (pin "1") (pinfunction "1_1") (pintype "input"))
      (node (ref "SW66") (pin "1") (pinfunction "1_1") (pintype "input"))
    )
    (net (code "15") (name "COL11") (class "Default")
      (node (ref "M1") (pin "27") (pinfunction "GPIO16_27") (pintype "bidirectional"))
      (node (ref "SW11") (pin "1") (pinfunction "1_1") (pintype "input"))
      (node (ref "SW20") (pin "1") (pinfunction "1_1") (pintype "input"))
      (node (ref "SW35") (pin "1") (pinfunction "1_1") (pintype "input"))
      (node (ref "SW50") (pin "1") (pinfunction "1_1") (pintype "input"))
      (node (ref "SW65") (pin "1") (pinfunction "1_1") (pintype "input"))
    )
    (net (code "16") (name "COL12") (class "Default")
      (node (ref "M1") (pin "28") (pinfunction "GPIO17_28") (pintype "bidirectional"))
      (node (ref "SW12") (pin "1") (pinfunction "1_1") (pintype "input"))
      (node (ref "SW19") (pin "1") (pinfunction "1_1") (pintype "input"))
      (node (ref "SW34") (pin "1") (pinfunction "1_1") (pintype "input"))
      (node (ref "SW49") (pin "1") (pinfunction "1_1") (pintype "input"))
      (node (ref "SW64") (pin "1") (pinfunction "1_1") (pintype "input"))
    )
    (net (code "17") (name "COL13") (class "Default")
      (node (ref "M1") (pin "29") (pinfunction "GPIO18_29") (pintype "bidirectional"))
      (node (ref "SW13") (pin "1") (pinfunction "1_1") (pintype "input"))
      (node (ref "SW18") (pin "1") (pinfunction "1_1") (pintype "input"))
      (node (ref "SW33") (pin "1") (pinfunction "1_1") (pintype "input"))
      (node (ref "SW48") (pin "1") (pinfunction "1_1") (pintype "input"))
    )
    (net (code "18") (name "COL14") (class "Default")
      (node (ref "M1") (pin "30") (pinfunction "GPIO19_30") (pintype "bidirectional"))
      (node (ref "SW14") (pin "1") (pinfunction "1_1") (pintype "input"))
      (node (ref "SW16") (pin "1") (pinfunction "1_1") (pintype "input"))
      (node (ref "SW31") (pin "1") (pinfunction "1_1") (pintype "input"))
    )
    (net (code "19") (name "COL15") (class "Default")
      (node (ref "M1") (pin "31") (pinfunction "GPIO20_31") (pintype "bidirectional"))
      (node (ref "SW15") (pin "1") (pinfunction "1_1") (pintype "input"))
    )
    (net (code "20") (name "GND") (class "Default")
      (node (ref "BT1") (pin "1") (pinfunction "A_1") (pintype "unspecified"))
      (node (ref "BT1") (pin "2") (pinfunction "B_2") (pintype "unspecified"))
      (node (ref "BT2") (pin "1") (pinfunction "A_1") (pintype "unspecified"))
      (node (ref "BT2") (pin "2") (pinfunction "B_2") (pintype "unspecified"))
      (node (ref "C1") (pin "1") (pinfunction "1_1") (pintype "input"))
      (node (ref "C10") (pin "1") (pinfunction "1_1") (pintype "unspecified"))
      (node (ref "C11") (pin "1") (pinfunction "1_1") (pintype "unspecified"))
      (node (ref "C12") (pin "1") (pinfunction "1_1") (pintype "unspecified"))
      (node (ref "C13") (pin "1") (pinfunction "1_1") (pintype "unspecified"))
      (node (ref "C14") (pin "1") (pinfunction "1_1") (pintype "unspecified"))
      (node (ref "C15") (pin "1") (pinfunction "1_1") (pintype "unspecified"))
      (node (ref "C16") (pin "1") (pinfunction "1_1") (pintype "unspecified"))
      (node (ref "C17") (pin "1") (pinfunction "1_1") (pintype "input"))
      (node (ref "C18") (pin "1") (pinfunction "1_1") (pintype "input"))
      (node (ref "C2") (pin "1") (pinfunction "1_1") (pintype "input"))
      (node (ref "C3") (pin "1") (pinfunction "1_1") (pintype "input"))
      (node (ref "C4") (pin "1") (pinfunction "1_1") (pintype "input"))
      (node (ref "C5") (pin "1") (pinfunction "1_1") (pintype "unspecified"))
      (node (ref "C6") (pin "2") (pinfunction "2_2") (pintype "input"))
      (node (ref "C7") (pin "1") (pinfunction "1_1") (pintype "input"))
      (node (ref "C8") (pin "1") (pinfunction "1_1") (pintype "input"))
      (node (ref "C9") (pin "1") (pinfunction "1_1") (pintype "unspecified"))
      (node (ref "LED1") (pin "2") (pinfunction "GND_2") (pintype "unspecified"))
      (node (ref "LED2") (pin "1") (pinfunction "K_1") (pintype "unspecified"))
      (node (ref "M1") (pin "19") (pinfunction "TESTEN_19") (pintype "unspecified"))
      (node (ref "M1") (pin "57") (pinfunction "GND_57") (pintype "bidirectional"))
      (node (ref "R1") (pin "1") (pinfunction "1_1") (pintype "input"))
      (node (ref "R2") (pin "1") (pinfunction "1_1") (pintype "input"))
      (node (ref "U2") (pin "2") (pinfunction "GND_2") (pintype "unspecified"))
      (node (ref "U3") (pin "4") (pinfunction "GND_4") (pintype "unspecified"))
      (node (ref "USBC") (pin "A12B1") (pinfunction "GND_A12B1") (pintype "unspecified"))
      (node (ref "USBC") (pin "A1B12") (pinfunction "GND_A1B12") (pintype "unspecified"))
      (node (ref "USBC") (pin "SH1") (pinfunction "SH1_SH1") (pintype "unspecified"))
      (node (ref "X1") (pin "2") (pinfunction "GND_2") (pintype "unspecified"))
      (node (ref "X1") (pin "4") (pinfunction "GND_4") (pintype "unspecified"))
    )
    (net (code "21") (name "Net-(D1-A)") (class "Default")
      (node (ref "D1") (pin "2") (pinfunction "A_2") (pintype "unspecified"))
      (node (ref "SW1") (pin "2") (pinfunction "2_2") (pintype "input"))
    )
    (net (code "22") (name "Net-(D2-A)") (class "Default")
      (node (ref "D2") (pin "2") (pinfunction "A_2") (pintype "unspecified"))
      (node (ref "SW2") (pin "2") (pinfunction "2_2") (pintype "input"))
    )
    (net (code "23") (name "Net-(D3-A)") (class "Default")
      (node (ref "D3") (pin "2") (pinfunction "A_2") (pintype "unspecified"))
      (node (ref "SW3") (pin "2") (pinfunction "2_2") (pintype "input"))
    )
    (net (code "24") (name "Net-(D4-A)") (class "Default")
      (node (ref "D4") (pin "2") (pinfunction "A_2") (pintype "unspecified"))
      (node (ref "SW4") (pin "2") (pinfunction "2_2") (pintype "input"))
    )
    (net (code "25") (name "Net-(D5-A)") (class "Default")
      (node (ref "D5") (pin "2") (pinfunction "A_2") (pintype "unspecified"))
      (node (ref "SW5") (pin "2") (pinfunction "2_2") (pintype "input"))
    )
    (net (code "26") (name "Net-(D6-A)") (class "Default")
      (node (ref "D6") (pin "2") (pinfunction "A_2") (pintype "unspecified"))
      (node (ref "SW6") (pin "2") (pinfunction "2_2") (pintype "input"))
    )
    (net (code "27") (name "Net-(D7-A)") (class "Default")
      (node (ref "D7") (pin "2") (pinfunction "A_2") (pintype "unspecified"))
      (node (ref "SW7") (pin "2") (pinfunction "2_2") (pintype "input"))
    )
    (net (code "28") (name "Net-(D8-A)") (class "Default")
      (node (ref "D8") (pin "2") (pinfunction "A_2") (pintype "unspecified"))
      (node (ref "SW8") (pin "2") (pinfunction "2_2") (pintype "input"))
    )
    (net (code "29") (name "Net-(D9-A)") (class "Default")
      (node (ref "D9") (pin "2") (pinfunction "A_2") (pintype "unspecified"))
      (node (ref "SW9") (pin "2") (pinfunction "2_2") (pintype "input"))
    )
    (net (code "30") (name "Net-(D10-A)") (class "Default")
      (node (ref "D10") (pin "2") (pinfunction "A_2") (pintype "unspecified"))
      (node (ref "SW10") (pin "2") (pinfunction "2_2") (pintype "input"))
    )
    (net (code "31") (name "Net-(D11-A)") (class "Default")
      (node (ref "D11") (pin "2") (pinfunction "A_2") (pintype "unspecified"))
      (node (ref "SW11") (pin "2") (pinfunction "2_2") (pintype "input"))
    )
    (net (code "32") (name "Net-(D12-A)") (class "Default")
      (node (ref "D12") (pin "2") (pinfunction "A_2") (pintype "unspecified"))
      (node (ref "SW12") (pin "2") (pinfunction "2_2") (pintype "input"))
    )
    (net (code "33") (name "Net-(D13-A)") (class "Default")
      (node (ref "D13") (pin "2") (pinfunction "A_2") (pintype "unspecified"))
      (node (ref "SW13") (pin "2") (pinfunction "2_2") (pintype "input"))
    )
    (net (code "34") (name "Net-(D14-A)") (class "Default")
      (node (ref "D14") (pin "2") (pinfunction "A_2") (pintype "unspecified"))
      (node (ref "SW14") (pin "2") (pinfunction "2_2") (pintype "input"))
    )
    (net (code "35") (name "Net-(D15-A)") (class "Default")
      (node (ref "D15") (pin "2") (pinfunction "A_2") (pintype "unspecified"))
      (node (ref "SW15") (pin "2") (pinfunction "2_2") (pintype "input"))
    )
    (net (code "36") (name "Net-(D16-A)") (class "Default")
      (node (ref "D16") (pin "2") (pinfunction "A_2") (pintype "unspecified"))
      (node (ref "SW16") (pin "2") (pinfunction "2_2") (pintype "input"))
    )
    (net (code "37") (name "Net-(D18-A)") (class "Default")
      (node (ref "D18") (pin "2") (pinfunction "A_2") (pintype "unspecified"))
      (node (ref "SW18") (pin "2") (pinfunction "2_2") (pintype "input"))
    )
    (net (code "38") (name "Net-(D19-A)") (class "Default")
      (node (ref "D19") (pin "2") (pinfunction "A_2") (pintype "unspecified"))
      (node (ref "SW19") (pin "2") (pinfunction "2_2") (pintype "input"))
    )
    (net (code "39") (name "Net-(D20-A)") (class "Default")
      (node (ref "D20") (pin "2") (pinfunction "A_2") (pintype "unspecified"))
      (node (ref "SW20") (pin "2") (pinfunction "2_2") (pintype "input"))
    )
    (net (code "40") (name "Net-(D21-A)") (class "Default")
      (node (ref "D21") (pin "2") (pinfunction "A_2") (pintype "unspecified"))
      (node (ref "SW21") (pin "2") (pinfunction "2_2") (pintype "input"))
    )
    (net (code "41") (name "Net-(D22-A)") (class "Default")
      (node (ref "D22") (pin "2") (pinfunction "A_2") (pintype "unspecified"))
      (node (ref "SW22") (pin "2") (pinfunction "2_2") (pintype "input"))
    )
    (net (code "42") (name "Net-(D23-A)") (class "Default")
      (node (ref "D23") (pin "2") (pinfunction "A_2") (pintype "unspecified"))
      (node (ref "SW23") (pin "2") (pinfunction "2_2") (pintype "input"))
    )
    (net (code "43") (name "Net-(D24-A)") (class "Default")
      (node (ref "D24") (pin "2") (pinfunction "A_2") (pintype "unspecified"))
      (node (ref "SW24") (pin "2") (pinfunction "2_2") (pintype "input"))
    )
    (net (code "44") (name "Net-(D25-A)") (class "Default")
      (node (ref "D25") (pin "2") (pinfunction "A_2") (pintype "unspecified"))
      (node (ref "SW25") (pin "2") (pinfunction "2_2") (pintype "input"))
    )
    (net (code "45") (name "Net-(D26-A)") (class "Default")
      (node (ref "D26") (pin "2") (pinfunction "A_2") (pintype "unspecified"))
      (node (ref "SW26") (pin "2") (pinfunction "2_2") (pintype "input"))
    )
    (net (code "46") (name "Net-(D27-A)") (class "Default")
      (node (ref "D27") (pin "2") (pinfunction "A_2") (pintype "unspecified"))
      (node (ref "SW27") (pin "2") (pinfunction "2_2") (pintype "input"))
    )
    (net (code "47") (name "Net-(D28-A)") (class "Default")
      (node (ref "D28") (pin "2") (pinfunction "A_2") (pintype "unspecified"))
      (node (ref "SW28") (pin "2") (pinfunction "2_2") (pintype "input"))
    )
    (net (code "48") (name "Net-(D29-A)") (class "Default")
      (node (ref "D29") (pin "2") (pinfunction "A_2") (pintype "unspecified"))
      (node (ref "SW29") (pin "2") (pinfunction "2_2") (pintype "input"))
    )
    (net (code "49") (name "Net-(D30-A)") (class "Default")
      (node (ref "D30") (pin "2") (pinfunction "A_2") (pintype "unspecified"))
      (node (ref "SW30") (pin "2") (pinfunction "2_2") (pintype "input"))
    )
    (net (code "50") (name "Net-(D31-A)") (class "Default")
      (node (ref "D31") (pin "2") (pinfunction "A_2") (pintype "unspecified"))
      (node (ref "SW31") (pin "2") (pinfunction "2_2") (pintype "input"))
    )
    (net (code "51") (name "Net-(D33-A)") (class "Default")
      (node (ref "D33") (pin "2") (pinfunction "A_2") (pintype "unspecified"))
      (node (ref "SW33") (pin "2") (pinfunction "2_2") (pintype "input"))
    )
    (net (code "52") (name "Net-(D34-A)") (class "Default")
      (node (ref "D34") (pin "2") (pinfunction "A_2") (pintype "unspecified"))
      (node (ref "SW34") (pin "2") (pinfunction "2_2") (pintype "input"))
    )
    (net (code "53") (name "Net-(D35-A)") (class "Default")
      (node (ref "D35") (pin "2") (pinfunction "A_2") (pintype "unspecified"))
      (node (ref "SW35") (pin "2") (pinfunction "2_2") (pintype "input"))
    )
    (net (code "54") (name "Net-(D36-A)") (class "Default")
      (node (ref "D36") (pin "2") (pinfunction "A_2") (pintype "unspecified"))
      (node (ref "SW36") (pin "2") (pinfunction "2_2") (pintype "input"))
    )
    (net (code "55") (name "Net-(D37-A)") (class "Default")
      (node (ref "D37") (pin "2") (pinfunction "A_2") (pintype "unspecified"))
      (node (ref "SW37") (pin "2") (pinfunction "2_2") (pintype "input"))
    )
    (net (code "56") (name "Net-(D38-A)") (class "Default")
      (node (ref "D38") (pin "2") (pinfunction "A_2") (pintype "unspecified"))
      (node (ref "SW38") (pin "2") (pinfunction "2_2") (pintype "input"))
    )
    (net (code "57") (name "Net-(D39-A)") (class "Default")
      (node (ref "D39") (pin "2") (pinfunction "A_2") (pintype "unspecified"))
      (node (ref "SW39") (pin "2") (pinfunction "2_2") (pintype "input"))
    )
    (net (code "58") (name "Net-(D40-A)") (class "Default")
      (node (ref "D40") (pin "2") (pinfunction "A_2") (pintype "unspecified"))
      (node (ref "SW40") (pin "2") (pinfunction "2_2") (pintype "input"))
    )
    (net (code "59") (name "Net-(D41-A)") (class "Default")
      (node (ref "D41") (pin "2") (pinfunction "A_2") (pintype "unspecified"))
      (node (ref "SW41") (pin "2") (pinfunction "2_2") (pintype "input"))
    )
    (net (code "60") (name "Net-(D42-A)") (class "Default")
      (node (ref "D42") (pin "2") (pinfunction "A_2") (pintype "unspecified"))
      (node (ref "SW42") (pin "2") (pinfunction "2_2") (pintype "input"))
    )
    (net (code "61") (name "Net-(D43-A)") (class "Default")
      (node (ref "D43") (pin "2") (pinfunction "A_2") (pintype "unspecified"))
      (node (ref "SW43") (pin "2") (pinfunction "2_2") (pintype "input"))
    )
    (net (code "62") (name "Net-(D44-A)") (class "Default")
      (node (ref "D44") (pin "2") (pinfunction "A_2") (pintype "unspecified"))
      (node (ref "SW44") (pin "2") (pinfunction "2_2") (pintype "input"))
    )
    (net (code "63") (name "Net-(D45-A)") (class "Default")
      (node (ref "D45") (pin "2") (pinfunction "A_2") (pintype "unspecified"))
      (node (ref "SW45") (pin "2") (pinfunction "2_2") (pintype "input"))
    )
    (net (code "64") (name "Net-(D48-A)") (class "Default")
      (node (ref "D48") (pin "2") (pinfunction "A_2") (pintype "unspecified"))
      (node (ref "SW48") (pin "2") (pinfunction "2_2") (pintype "input"))
    )
    (net (code "65") (name "Net-(D49-A)") (class "Default")
      (node (ref "D49") (pin "2") (pinfunction "A_2") (pintype "unspecified"))
      (node (ref "SW49") (pin "2") (pinfunction "2_2") (pintype "input"))
    )
    (net (code "66") (name "Net-(D50-A)") (class "Default")
      (node (ref "D50") (pin "2") (pinfunction "A_2") (pintype "unspecified"))
      (node (ref "SW50") (pin "2") (pinfunction "2_2") (pintype "input"))
    )
    (net (code "67") (name "Net-(D51-A)") (class "Default")
      (node (ref "D51") (pin "2") (pinfunction "A_2") (pintype "unspecified"))
      (node (ref "SW51") (pin "2") (pinfunction "2_2") (pintype "input"))
    )
    (net (code "68") (name "Net-(D52-A)") (class "Default")
      (node (ref "D52") (pin "2") (pinfunction "A_2") (pintype "unspecified"))
      (node (ref "SW52") (pin "2") (pinfunction "2_2") (pintype "input"))
    )
    (net (code "69") (name "Net-(D53-A)") (class "Default")
      (node (ref "D53") (pin "2") (pinfunction "A_2") (pintype "unspecified"))
      (node (ref "SW53") (pin "2") (pinfunction "2_2") (pintype "input"))
    )
    (net (code "70") (name "Net-(D54-A)") (class "Default")
      (node (ref "D54") (pin "2") (pinfunction "A_2") (pintype "unspecified"))
      (node (ref "SW54") (pin "2") (pinfunction "2_2") (pintype "input"))
    )
    (net (code "71") (name "Net-(D55-A)") (class "Default")
      (node (ref "D55") (pin "2") (pinfunction "A_2") (pintype "unspecified"))
      (node (ref "SW55") (pin "2") (pinfunction "2_2") (pintype "input"))
    )
    (net (code "72") (name "Net-(D56-A)") (class "Default")
      (node (ref "D56") (pin "2") (pinfunction "A_2") (pintype "unspecified"))
      (node (ref "SW56") (pin "2") (pinfunction "2_2") (pintype "input"))
    )
    (net (code "73") (name "Net-(D57-A)") (class "Default")
      (node (ref "D57") (pin "2") (pinfunction "A_2") (pintype "unspecified"))
      (node (ref "SW57") (pin "2") (pinfunction "2_2") (pintype "input"))
    )
    (net (code "74") (name "Net-(D58-A)") (class "Default")
      (node (ref "D58") (pin "2") (pinfunction "A_2") (pintype "unspecified"))
      (node (ref "SW58") (pin "2") (pinfunction "2_2") (pintype "input"))
    )
    (net (code "75") (name "Net-(D59-A)") (class "Default")
      (node (ref "D59") (pin "2") (pinfunction "A_2") (pintype "unspecified"))
      (node (ref "SW59") (pin "2") (pinfunction "2_2") (pintype "input"))
    )
    (net (code "76") (name "Net-(D60-A)") (class "Default")
      (node (ref "D60") (pin "2") (pinfunction "A_2") (pintype "unspecified"))
      (node (ref "SW60") (pin "2") (pinfunction "2_2") (pintype "input"))
    )
    (net (code "77") (name "Net-(D64-A)") (class "Default")
      (node (ref "D64") (pin "2") (pinfunction "A_2") (pintype "unspecified"))
      (node (ref "SW64") (pin "2") (pinfunction "2_2") (pintype "input"))
    )
    (net (code "78") (name "Net-(D65-A)") (class "Default")
      (node (ref "D65") (pin "2") (pinfunction "A_2") (pintype "unspecified"))
      (node (ref "SW65") (pin "2") (pinfunction "2_2") (pintype "input"))
    )
    (net (code "79") (name "Net-(D66-A)") (class "Default")
      (node (ref "D66") (pin "2") (pinfunction "A_2") (pintype "unspecified"))
      (node (ref "SW66") (pin "2") (pinfunction "2_2") (pintype "input"))
    )
    (net (code "80") (name "Net-(D67-A)") (class "Default")
      (node (ref "D67") (pin "2") (pinfunction "A_2") (pintype "unspecified"))
      (node (ref "SW67") (pin "2") (pinfunction "2_2") (pintype "input"))
    )
    (net (code "81") (name "Net-(D68-A)") (class "Default")
      (node (ref "D68") (pin "2") (pinfunction "A_2") (pintype "unspecified"))
      (node (ref "SW68") (pin "2") (pinfunction "2_2") (pintype "input"))
    )
    (net (code "82") (name "Net-(D69-A)") (class "Default")
      (node (ref "D69") (pin "2") (pinfunction "A_2") (pintype "unspecified"))
      (node (ref "SW69") (pin "2") (pinfunction "2_2") (pintype "input"))
    )
    (net (code "83") (name "Net-(D70-A)") (class "Default")
      (node (ref "D70") (pin "2") (pinfunction "A_2") (pintype "unspecified"))
      (node (ref "SW70") (pin "2") (pinfunction "2_2") (pintype "input"))
    )
    (net (code "84") (name "Net-(D71-A)") (class "Default")
      (node (ref "D71") (pin "2") (pinfunction "A_2") (pintype "unspecified"))
      (node (ref "SW71") (pin "2") (pinfunction "2_2") (pintype "input"))
    )
    (net (code "85") (name "Net-(D72-A)") (class "Default")
      (node (ref "D72") (pin "2") (pinfunction "A_2") (pintype "unspecified"))
      (node (ref "SW72") (pin "2") (pinfunction "2_2") (pintype "input"))
    )
    (net (code "86") (name "Net-(D73-A)") (class "Default")
      (node (ref "D73") (pin "2") (pinfunction "A_2") (pintype "unspecified"))
      (node (ref "SW73") (pin "2") (pinfunction "2_2") (pintype "input"))
    )
    (net (code "87") (name "Net-(D74-A)") (class "Default")
      (node (ref "D74") (pin "2") (pinfunction "A_2") (pintype "unspecified"))
      (node (ref "SW74") (pin "2") (pinfunction "2_2") (pintype "input"))
    )
    (net (code "88") (name "Net-(D75-A)") (class "Default")
      (node (ref "D75") (pin "2") (pinfunction "A_2") (pintype "unspecified"))
      (node (ref "SW75") (pin "2") (pinfunction "2_2") (pintype "input"))
    )
    (net (code "89") (name "Net-(D83-A)") (class "Default")
      (node (ref "D83") (pin "2") (pinfunction "A_2") (pintype "unspecified"))
      (node (ref "SW83") (pin "2") (pinfunction "2_2") (pintype "input"))
    )
    (net (code "90") (name "Net-(D84-A)") (class "Default")
      (node (ref "D84") (pin "2") (pinfunction "A_2") (pintype "unspecified"))
      (node (ref "SW84") (pin "2") (pinfunction "2_2") (pintype "input"))
    )
    (net (code "91") (name "Net-(D85-A)") (class "Default")
      (node (ref "D85") (pin "2") (pinfunction "A_2") (pintype "unspecified"))
      (node (ref "SW85") (pin "2") (pinfunction "2_2") (pintype "input"))
    )
    (net (code "92") (name "Net-(D86-A)") (class "Default")
      (node (ref "D86") (pin "2") (pinfunction "A_2") (pintype "unspecified"))
      (node (ref "SW86") (pin "2") (pinfunction "2_2") (pintype "input"))
    )
    (net (code "93") (name "Net-(D87-A)") (class "Default")
      (node (ref "D87") (pin "2") (pinfunction "A_2") (pintype "unspecified"))
      (node (ref "SW87") (pin "2") (pinfunction "2_2") (pintype "input"))
    )
    (net (code "94") (name "Net-(D88-A)") (class "Default")
      (node (ref "D88") (pin "2") (pinfunction "A_2") (pintype "unspecified"))
      (node (ref "SW88") (pin "2") (pinfunction "2_2") (pintype "input"))
    )
    (net (code "95") (name "Net-(D89-A)") (class "Default")
      (node (ref "D89") (pin "2") (pinfunction "A_2") (pintype "unspecified"))
      (node (ref "SW89") (pin "2") (pinfunction "2_2") (pintype "input"))
    )
    (net (code "96") (name "Net-(D90-A)") (class "Default")
      (node (ref "D90") (pin "2") (pinfunction "A_2") (pintype "unspecified"))
      (node (ref "SW90") (pin "2") (pinfunction "2_2") (pintype "input"))
    )
    (net (code "97") (name "Net-(LED2-A)") (class "Default")
      (node (ref "LED2") (pin "2") (pinfunction "A_2") (pintype "unspecified"))
      (node (ref "R3") (pin "1") (pinfunction "1_1") (pintype "input"))
    )
    (net (code "98") (name "Net-(M1-ADC_AVDD)") (class "Default")
      (node (ref "C8") (pin "2") (pinfunction "2_2") (pintype "input"))
      (node (ref "M1") (pin "43") (pinfunction "ADC_AVDD_43") (pintype "bidirectional"))
      (node (ref "R9") (pin "2") (pinfunction "2_2") (pintype "input"))
    )
    (net (code "99") (name "Net-(M1-USB_DM)") (class "Default")
      (node (ref "M1") (pin "46") (pinfunction "USB_DM_46") (pintype "bidirectional"))
      (node (ref "R8") (pin "1") (pinfunction "1_1") (pintype "input"))
    )
    (net (code "100") (name "Net-(M1-USB_DP)") (class "Default")
      (node (ref "M1") (pin "47") (pinfunction "USB_DP_47") (pintype "bidirectional"))
      (node (ref "R7") (pin "1") (pinfunction "1_1") (pintype "input"))
    )
    (net (code "101") (name "Net-(M1-XIN)") (class "Default")
      (node (ref "C6") (pin "1") (pinfunction "1_1") (pintype "input"))
      (node (ref "M1") (pin "20") (pinfunction "XIN_20") (pintype "input"))
      (node (ref "X1") (pin "3") (pinfunction "OSC2_3") (pintype "unspecified"))
    )
    (net (code "102") (name "Net-(M1-XOUT)") (class "Default")
      (node (ref "C7") (pin "2") (pinfunction "2_2") (pintype "input"))
      (node (ref "M1") (pin "21") (pinfunction "XOUT_21") (pintype "unspecified"))
      (node (ref "X1") (pin "1") (pinfunction "OSC1_1") (pintype "unspecified"))
    )
    (net (code "103") (name "Net-(USBC-CC1)") (class "Default")
      (node (ref "R2") (pin "2") (pinfunction "2_2") (pintype "input"))
      (node (ref "USBC") (pin "A5") (pinfunction "CC1_A5") (pintype "unspecified"))
    )
    (net (code "104") (name "Net-(USBC-CC2)") (class "Default")
      (node (ref "R1") (pin "2") (pinfunction "2_2") (pintype "input"))
      (node (ref "USBC") (pin "B5") (pinfunction "CC2_B5") (pintype "unspecified"))
    )
    (net (code "105") (name "QSPI-0") (class "Default")
      (node (ref "M1") (pin "53") (pinfunction "QSPI_SD0_53") (pintype "bidirectional"))
      (node (ref "U3") (pin "5") (pinfunction "DI_5") (pintype "unspecified"))
    )
    (net (code "106") (name "QSPI-1") (class "Default")
      (node (ref "M1") (pin "55") (pinfunction "QSPI_SD1_55") (pintype "bidirectional"))
      (node (ref "U3") (pin "2") (pinfunction "DO_2") (pintype "unspecified"))
    )
    (net (code "107") (name "QSPI-2") (class "Default")
      (node (ref "M1") (pin "54") (pinfunction "QSPI_SD2_54") (pintype "bidirectional"))
      (node (ref "U3") (pin "3") (pinfunction "IO2_3") (pintype "unspecified"))
    )
    (net (code "108") (name "QSPI-3") (class "Default")
      (node (ref "M1") (pin "51") (pinfunction "QSPI_SD3_51") (pintype "bidirectional"))
      (node (ref "U3") (pin "7") (pinfunction "IO3_7") (pintype "unspecified"))
    )
    (net (code "109") (name "QSPI-CLK") (class "Default")
      (node (ref "M1") (pin "52") (pinfunction "QSPI_SCLK_52") (pintype "output"))
      (node (ref "U3") (pin "6") (pinfunction "CLK_6") (pintype "unspecified"))
    )
    (net (code "110") (name "QSPI-CS") (class "Default")
      (node (ref "M1") (pin "56") (pinfunction "QSPI_SS_56") (pintype "bidirectional"))
      (node (ref "R5") (pin "1") (pinfunction "1_1") (pintype "input"))
      (node (ref "R6") (pin "1") (pinfunction "1_1") (pintype "input"))
      (node (ref "U3") (pin "1") (pinfunction "CS#_1") (pintype "unspecified"))
    )
    (net (code "111") (name "RAW") (class "Default")
      (node (ref "C3") (pin "2") (pinfunction "2_2") (pintype "input"))
      (node (ref "F1") (pin "2") (pinfunction "2_2") (pintype "unspecified"))
      (node (ref "LED1") (pin "4") (pinfunction "VDD_4") (pintype "unspecified"))
      (node (ref "U2") (pin "1") (pinfunction "VIN_1") (pintype "unspecified"))
      (node (ref "U2") (pin "3") (pinfunction "EN_3") (pintype "unspecified"))
    )
    (net (code "112") (name "RESET") (class "Default")
      (node (ref "BT2") (pin "3") (pinfunction "C_3") (pintype "unspecified"))
      (node (ref "BT2") (pin "4") (pinfunction "D_4") (pintype "unspecified"))
      (node (ref "M1") (pin "26") (pinfunction "RUN_26") (pintype "input"))
      (node (ref "R4") (pin "1") (pinfunction "1_1") (pintype "input"))
    )
    (net (code "113") (name "ROW1") (class "Default")
      (node (ref "D1") (pin "1") (pinfunction "K_1") (pintype "unspecified"))
      (node (ref "D10") (pin "1") (pinfunction "K_1") (pintype "unspecified"))
      (node (ref "D11") (pin "1") (pinfunction "K_1") (pintype "unspecified"))
      (node (ref "D12") (pin "1") (pinfunction "K_1") (pintype "unspecified"))
      (node (ref "D13") (pin "1") (pinfunction "K_1") (pintype "unspecified"))
      (node (ref "D14") (pin "1") (pinfunction "K_1") (pintype "unspecified"))
      (node (ref "D15") (pin "1") (pinfunction "K_1") (pintype "unspecified"))
      (node (ref "D2") (pin "1") (pinfunction "K_1") (pintype "unspecified"))
      (node (ref "D3") (pin "1") (pinfunction "K_1") (pintype "unspecified"))
      (node (ref "D4") (pin "1") (pinfunction "K_1") (pintype "unspecified"))
      (node (ref "D5") (pin "1") (pinfunction "K_1") (pintype "unspecified"))
      (node (ref "D6") (pin "1") (pinfunction "K_1") (pintype "unspecified"))
      (node (ref "D7") (pin "1") (pinfunction "K_1") (pintype "unspecified"))
      (node (ref "D8") (pin "1") (pinfunction "K_1") (pintype "unspecified"))
      (node (ref "D9") (pin "1") (pinfunction "K_1") (pintype "unspecified"))
      (node (ref "M1") (pin "2") (pinfunction "GPIO0_2") (pintype "bidirectional"))
    )
    (net (code "114") (name "ROW2") (class "Default")
      (node (ref "D16") (pin "1") (pinfunction "K_1") (pintype "unspecified"))
      (node (ref "D18") (pin "1") (pinfunction "K_1") (pintype "unspecified"))
      (node (ref "D19") (pin "1") (pinfunction "K_1") (pintype "unspecified"))
      (node (ref "D20") (pin "1") (pinfunction "K_1") (pintype "unspecified"))
      (node (ref "D21") (pin "1") (pinfunction "K_1") (pintype "unspecified"))
      (node (ref "D22") (pin "1") (pinfunction "K_1") (pintype "unspecified"))
      (node (ref "D23") (pin "1") (pinfunction "K_1") (pintype "unspecified"))
      (node (ref "D24") (pin "1") (pinfunction "K_1") (pintype "unspecified"))
      (node (ref "D25") (pin "1") (pinfunction "K_1") (pintype "unspecified"))
      (node (ref "D26") (pin "1") (pinfunction "K_1") (pintype "unspecified"))
      (node (ref "D27") (pin "1") (pinfunction "K_1") (pintype "unspecified"))
      (node (ref "D28") (pin "1") (pinfunction "K_1") (pintype "unspecified"))
      (node (ref "D29") (pin "1") (pinfunction "K_1") (pintype "unspecified"))
      (node (ref "D30") (pin "1") (pinfunction "K_1") (pintype "unspecified"))
      (node (ref "M1") (pin "3") (pinfunction "GPIO1_3") (pintype "bidirectional"))
    )
    (net (code "115") (name "ROW3") (class "Default")
      (node (ref "D31") (pin "1") (pinfunction "K_1") (pintype "unspecified"))
      (node (ref "D33") (pin "1") (pinfunction "K_1") (pintype "unspecified"))
      (node (ref "D34") (pin "1") (pinfunction "K_1") (pintype "unspecified"))
      (node (ref "D35") (pin "1") (pinfunction "K_1") (pintype "unspecified"))
      (node (ref "D36") (pin "1") (pinfunction "K_1") (pintype "unspecified"))
      (node (ref "D37") (pin "1") (pinfunction "K_1") (pintype "unspecified"))
      (node (ref "D38") (pin "1") (pinfunction "K_1") (pintype "unspecified"))
      (node (ref "D39") (pin "1") (pinfunction "K_1") (pintype "unspecified"))
      (node (ref "D40") (pin "1") (pinfunction "K_1") (pintype "unspecified"))
      (node (ref "D41") (pin "1") (pinfunction "K_1") (pintype "unspecified"))
      (node (ref "D42") (pin "1") (pinfunction "K_1") (pintype "unspecified"))
      (node (ref "D43") (pin "1") (pinfunction "K_1") (pintype "unspecified"))
      (node (ref "D44") (pin "1") (pinfunction "K_1") (pintype "unspecified"))
      (node (ref "D45") (pin "1") (pinfunction "K_1") (pintype "unspecified"))
      (node (ref "M1") (pin "4") (pinfunction "GPIO2_4") (pintype "bidirectional"))
    )
    (net (code "116") (name "ROW4") (class "Default")
      (node (ref "D48") (pin "1") (pinfunction "K_1") (pintype "unspecified"))
      (node (ref "D49") (pin "1") (pinfunction "K_1") (pintype "unspecified"))
      (node (ref "D50") (pin "1") (pinfunction "K_1") (pintype "unspecified"))
      (node (ref "D51") (pin "1") (pinfunction "K_1") (pintype "unspecified"))
      (node (ref "D52") (pin "1") (pinfunction "K_1") (pintype "unspecified"))
      (node (ref "D53") (pin "1") (pinfunction "K_1") (pintype "unspecified"))
      (node (ref "D54") (pin "1") (pinfunction "K_1") (pintype "unspecified"))
      (node (ref "D55") (pin "1") (pinfunction "K_1") (pintype "unspecified"))
      (node (ref "D56") (pin "1") (pinfunction "K_1") (pintype "unspecified"))
      (node (ref "D57") (pin "1") (pinfunction "K_1") (pintype "unspecified"))
      (node (ref "D58") (pin "1") (pinfunction "K_1") (pintype "unspecified"))
      (node (ref "D59") (pin "1") (pinfunction "K_1") (pintype "unspecified"))
      (node (ref "D60") (pin "1") (pinfunction "K_1") (pintype "unspecified"))
      (node (ref "M1") (pin "5") (pinfunction "GPIO3_5") (pintype "bidirectional"))
    )
    (net (code "117") (name "ROW5") (class "Default")
      (node (ref "D64") (pin "1") (pinfunction "K_1") (pintype "unspecified"))
      (node (ref "D65") (pin "1") (pinfunction "K_1") (pintype "unspecified"))
      (node (ref "D66") (pin "1") (pinfunction "K_1") (pintype "unspecified"))
      (node (ref "D67") (pin "1") (pinfunction "K_1") (pintype "unspecified"))
      (node (ref "D68") (pin "1") (pinfunction "K_1") (pintype "unspecified"))
      (node (ref "D69") (pin "1") (pinfunction "K_1") (pintype "unspecified"))
      (node (ref "D70") (pin "1") (pinfunction "K_1") (pintype "unspecified"))
      (node (ref "D71") (pin "1") (pinfunction "K_1") (pintype "unspecified"))
      (node (ref "D72") (pin "1") (pinfunction "K_1") (pintype "unspecified"))
      (node (ref "D73") (pin "1") (pinfunction "K_1") (pintype "unspecified"))
      (node (ref "D74") (pin "1") (pinfunction "K_1") (pintype "unspecified"))
      (node (ref "D75") (pin "1") (pinfunction "K_1") (pintype "unspecified"))
      (node (ref "M1") (pin "6") (pinfunction "GPIO4_6") (pintype "bidirectional"))
    )
    (net (code "118") (name "ROW6") (class "Default")
      (node (ref "D83") (pin "1") (pinfunction "K_1") (pintype "unspecified"))
      (node (ref "D84") (pin "1") (pinfunction "K_1") (pintype "unspecified"))
      (node (ref "D85") (pin "1") (pinfunction "K_1") (pintype "unspecified"))
      (node (ref "D86") (pin "1") (pinfunction "K_1") (pintype "unspecified"))
      (node (ref "D87") (pin "1") (pinfunction "K_1") (pintype "unspecified"))
      (node (ref "D88") (pin "1") (pinfunction "K_1") (pintype "unspecified"))
      (node (ref "D89") (pin "1") (pinfunction "K_1") (pintype "unspecified"))
      (node (ref "D90") (pin "1") (pinfunction "K_1") (pintype "unspecified"))
      (node (ref "M1") (pin "7") (pinfunction "GPIO5_7") (pintype "bidirectional"))
    )
    (net (code "119") (name "RP_D+") (class "Default")
      (node (ref "R7") (pin "2") (pinfunction "2_2") (pintype "input"))
      (node (ref "USBC") (pin "A6") (pinfunction "DP1_A6") (pintype "unspecified"))
      (node (ref "USBC") (pin "B6") (pinfunction "DP2_B6") (pintype "unspecified"))
    )
    (net (code "120") (name "RP_D-") (class "Default")
      (node (ref "R8") (pin "2") (pinfunction "2_2") (pintype "input"))
      (node (ref "USBC") (pin "A7") (pinfunction "DN1_A7") (pintype "unspecified"))
      (node (ref "USBC") (pin "B7") (pinfunction "DN2_B7") (pintype "unspecified"))
    )
    (net (code "121") (name "V_USB") (class "Default")
      (node (ref "C1") (pin "2") (pinfunction "2_2") (pintype "input"))
      (node (ref "F1") (pin "1") (pinfunction "1_1") (pintype "unspecified"))
      (node (ref "USBC") (pin "A4B9") (pinfunction "VBUS_A4B9") (pintype "unspecified"))
      (node (ref "USBC") (pin "A9B4") (pinfunction "VBUS_A9B4") (pintype "unspecified"))
    )
    (net (code "122") (name "unconnected-(LED1-DO-Pad1)") (class "Default")
      (node (ref "LED1") (pin "1") (pinfunction "DO_1") (pintype "unspecified+no_connect"))
    )
    (net (code "123") (name "unconnected-(M1-GPIO21-Pad32)") (class "Default")
      (node (ref "M1") (pin "32") (pinfunction "GPIO21_32") (pintype "bidirectional+no_connect"))
    )
    (net (code "124") (name "unconnected-(M1-GPIO22-Pad34)") (class "Default")
      (node (ref "M1") (pin "34") (pinfunction "GPIO22_34") (pintype "bidirectional+no_connect"))
    )
    (net (code "125") (name "unconnected-(M1-GPIO23-Pad35)") (class "Default")
      (node (ref "M1") (pin "35") (pinfunction "GPIO23_35") (pintype "bidirectional+no_connect"))
    )
    (net (code "126") (name "unconnected-(M1-GPIO24-Pad36)") (class "Default")
      (node (ref "M1") (pin "36") (pinfunction "GPIO24_36") (pintype "bidirectional+no_connect"))
    )
    (net (code "127") (name "unconnected-(M1-GPIO26_ADC0-Pad38)") (class "Default")
      (node (ref "M1") (pin "38") (pinfunction "GPIO26_ADC0_38") (pintype "bidirectional+no_connect"))
    )
    (net (code "128") (name "unconnected-(M1-GPIO27_ADC1-Pad39)") (class "Default")
      (node (ref "M1") (pin "39") (pinfunction "GPIO27_ADC1_39") (pintype "bidirectional+no_connect"))
    )
    (net (code "129") (name "unconnected-(M1-GPIO28_ADC2-Pad40)") (class "Default")
      (node (ref "M1") (pin "40") (pinfunction "GPIO28_ADC2_40") (pintype "bidirectional+no_connect"))
    )
    (net (code "130") (name "unconnected-(M1-GPIO29_ADC3-Pad41)") (class "Default")
      (node (ref "M1") (pin "41") (pinfunction "GPIO29_ADC3_41") (pintype "bidirectional+no_connect"))
    )
    (net (code "131") (name "unconnected-(M1-SWCLK-Pad24)") (class "Default")
      (node (ref "M1") (pin "24") (pinfunction "SWCLK_24") (pintype "output+no_connect"))
    )
    (net (code "132") (name "unconnected-(M1-SWD-Pad25)") (class "Default")
      (node (ref "M1") (pin "25") (pinfunction "SWD_25") (pintype "bidirectional+no_connect"))
    )
    (net (code "133") (name "unconnected-(U2-NC-Pad4)") (class "Default")
      (node (ref "U2") (pin "4") (pinfunction "NC_4") (pintype "unspecified+no_connect"))
    )
    (net (code "134") (name "unconnected-(USBC-SBU1-PadA8)") (class "Default")
      (node (ref "USBC") (pin "A8") (pinfunction "SBU1_A8") (pintype "unspecified+no_connect"))
    )
    (net (code "135") (name "unconnected-(USBC-SBU2-PadB8)") (class "Default")
      (node (ref "USBC") (pin "B8") (pinfunction "SBU2_B8") (pintype "unspecified+no_connect"))
    )
  )
)
